# 40-.net
KiCad netlist of a schematic drawn in Altium Designer
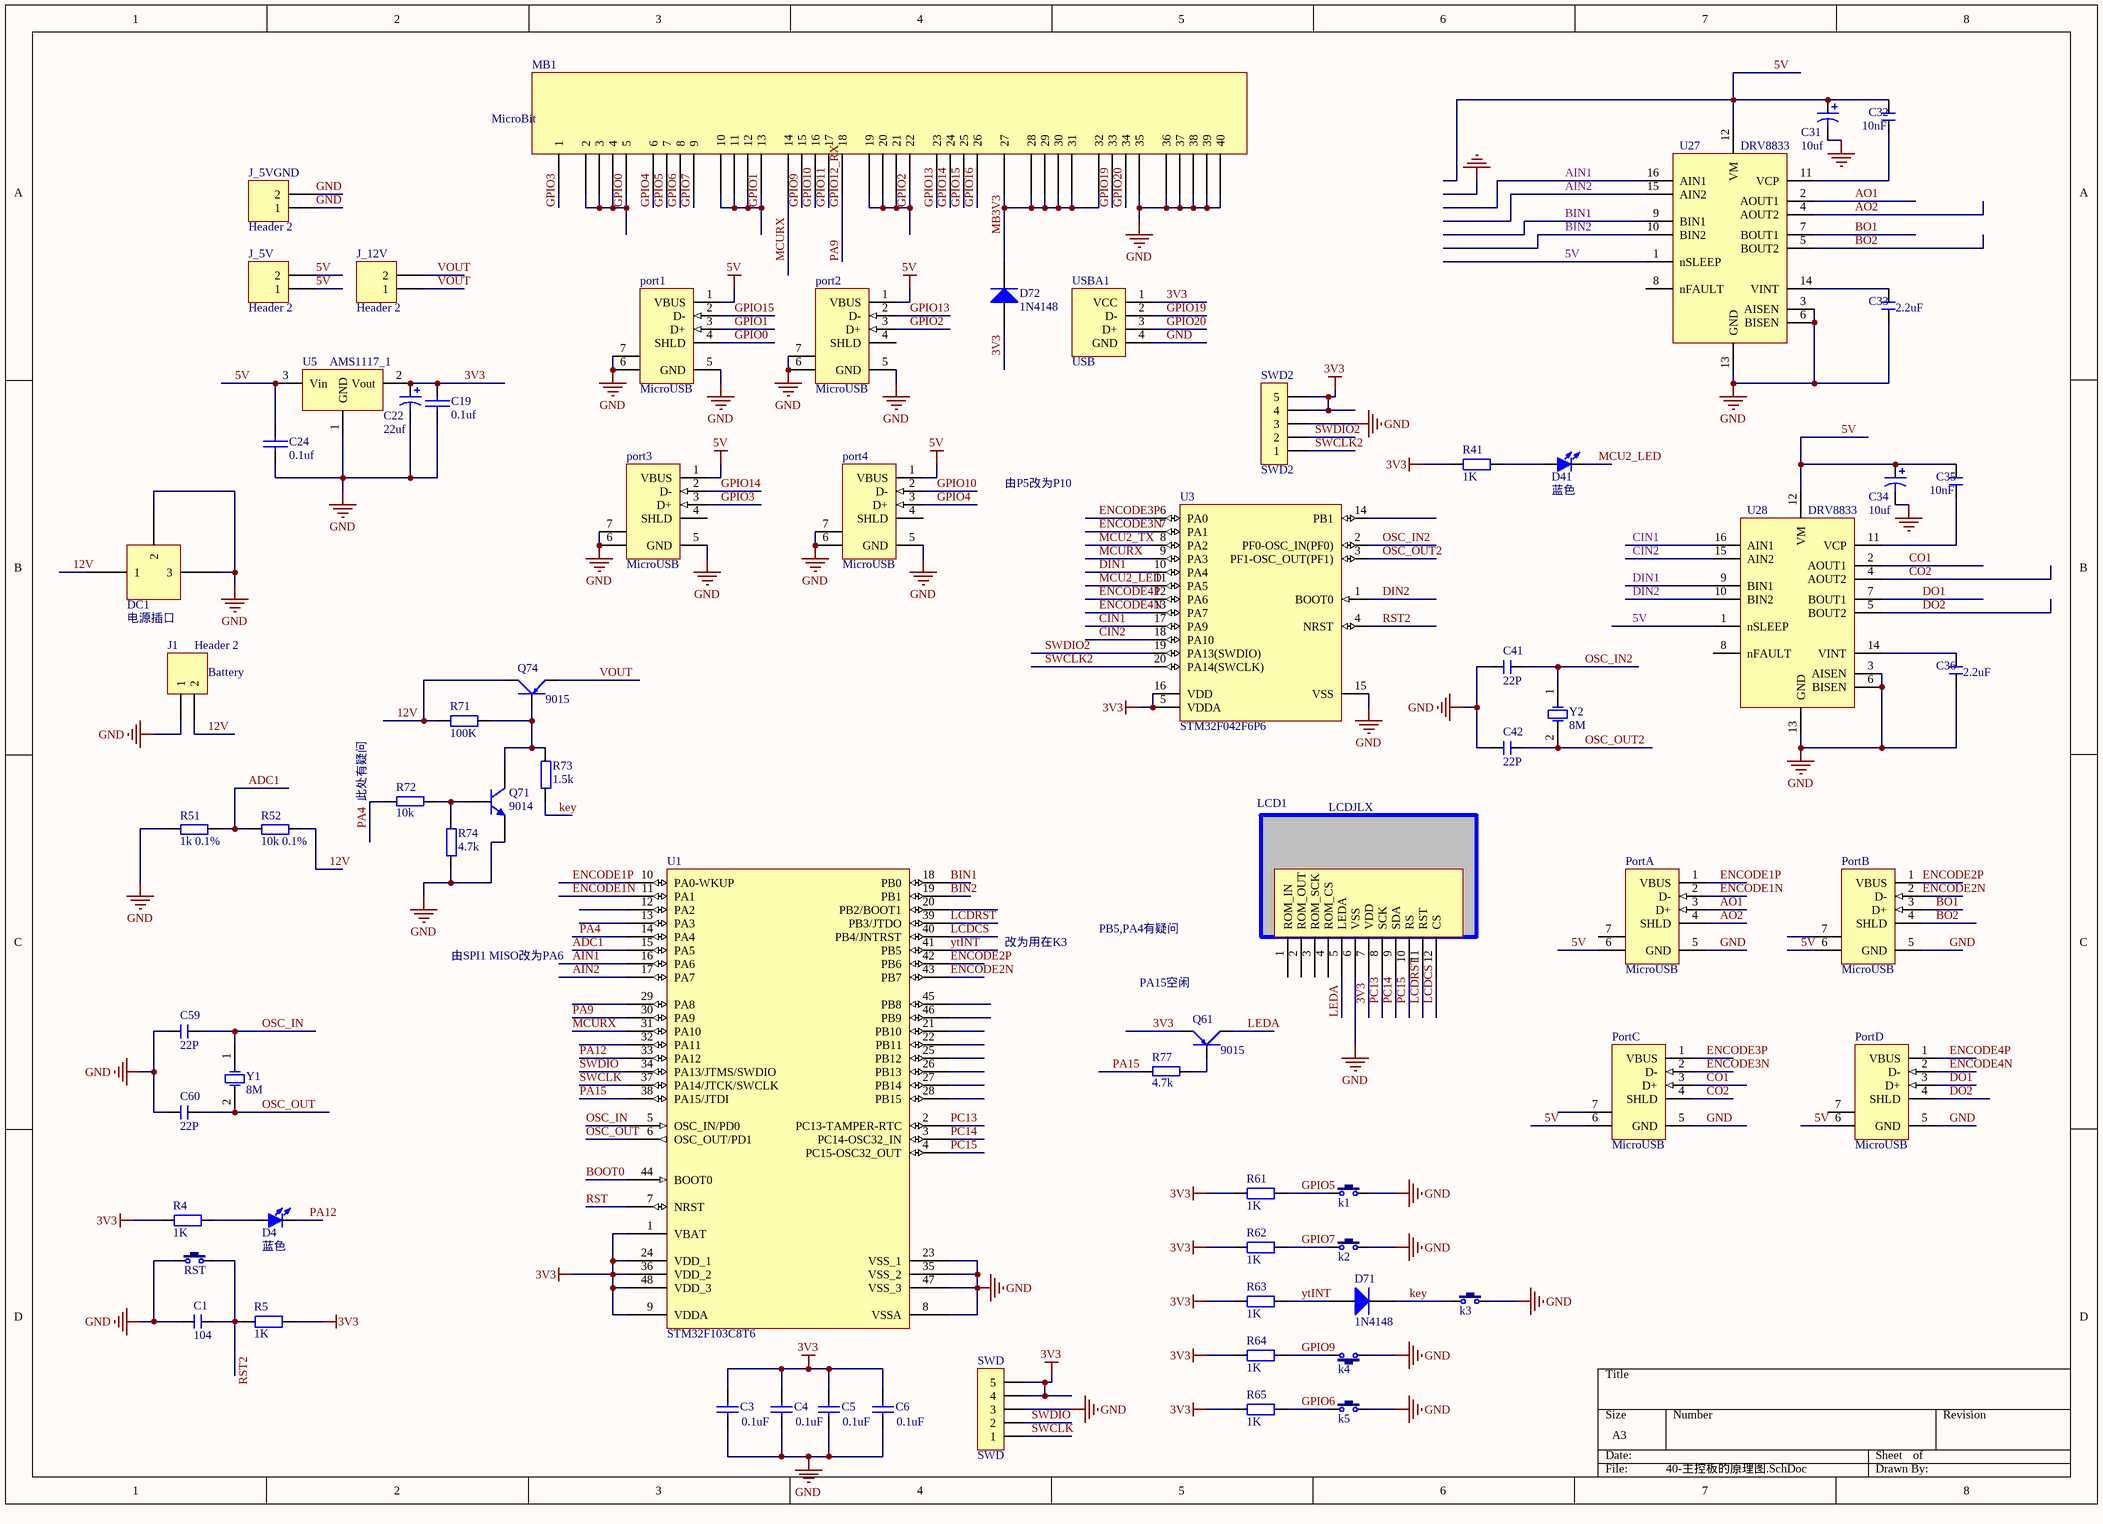
[diagram p0: 40-主控板的原理图.SchDoc]

(export (version "E")
  (design (tool "Eeschema 10.0.6"))
  (components
    (comp (ref "C1")
      (value "104")
      (footprint "C0603")
      (description "无极性贴片电容")
      (libsource (lib "3.1   - 电阻-电容-电感") (part "C"))
    )
    (comp (ref "C3")
      (value "0.1uF")
      (footprint "C0603")
      (description "Capacitor")
      (fields (field (name "Comment") "0.1uf") (field (name "PUBLISHER") "Altium Limited"))
      (libsource (lib "Miscellaneous Devices") (part "Cap"))
    )
    (comp (ref "C4")
      (value "0.1uF")
      (footprint "C0603")
      (description "Capacitor")
      (fields (field (name "Comment") "0.1uf") (field (name "PUBLISHER") "Altium Limited"))
      (libsource (lib "Miscellaneous Devices") (part "Cap"))
    )
    (comp (ref "C5")
      (value "0.1uF")
      (footprint "C0603")
      (description "Capacitor")
      (fields (field (name "Comment") "0.1uf") (field (name "PUBLISHER") "Altium Limited"))
      (libsource (lib "Miscellaneous Devices") (part "Cap"))
    )
    (comp (ref "C6")
      (value "0.1uF")
      (footprint "C0603")
      (description "Capacitor")
      (fields (field (name "Comment") "0.1uf") (field (name "PUBLISHER") "Altium Limited"))
      (libsource (lib "Miscellaneous Devices") (part "Cap"))
    )
    (comp (ref "C19") (value "0.1uf") (footprint "LC-0603_C") (libsource (lib "自创") (part "CAP")))
    (comp (ref "C22")
      (value "22uf")
      (footprint "CD B(3528)")
      (description "Polarized Capacitor (Axial)")
      (fields (field (name "PUBLISHER") "Altium Limited"))
      (libsource (lib "自创") (part "Cap Pol2"))
    )
    (comp (ref "C24") (value "0.1uf") (footprint "LC-0603_C") (libsource (lib "自创") (part "CAP")))
    (comp (ref "C31")
      (value "10uf")
      (footprint "CD B(3528)")
      (description "Polarized Capacitor (Axial)")
      (fields (field (name "PUBLISHER") "Altium Limited"))
      (libsource (lib "自创") (part "Cap Pol2"))
    )
    (comp (ref "C32")
      (value "10nF")
      (footprint "C0603")
      (description "无极性贴片电容")
      (libsource (lib "电阻-电容-电感") (part "C"))
    )
    (comp (ref "C33")
      (value "2.2uF")
      (footprint "C0603")
      (description "无极性贴片电容")
      (libsource (lib "电阻-电容-电感") (part "C"))
    )
    (comp (ref "C34")
      (value "10uf")
      (footprint "CD B(3528)")
      (description "Polarized Capacitor (Axial)")
      (fields (field (name "PUBLISHER") "Altium Limited"))
      (libsource (lib "自创") (part "Cap Pol2"))
    )
    (comp (ref "C35")
      (value "10nF")
      (footprint "C0603")
      (description "无极性贴片电容")
      (libsource (lib "电阻-电容-电感") (part "C"))
    )
    (comp (ref "C36")
      (value "2.2uF")
      (footprint "C0603")
      (description "无极性贴片电容")
      (libsource (lib "电阻-电容-电感") (part "C"))
    )
    (comp (ref "C41")
      (value "22P")
      (footprint "C0603")
      (description "无极性贴片电容")
      (libsource (lib "3.1   - 电阻-电容-电感") (part "C"))
    )
    (comp (ref "C42")
      (value "22P")
      (footprint "C0603")
      (description "无极性贴片电容")
      (libsource (lib "3.1   - 电阻-电容-电感") (part "C"))
    )
    (comp (ref "C59")
      (value "22P")
      (footprint "C0603")
      (description "无极性贴片电容")
      (libsource (lib "3.1   - 电阻-电容-电感") (part "C"))
    )
    (comp (ref "C60")
      (value "22P")
      (footprint "C0603")
      (description "无极性贴片电容")
      (libsource (lib "3.1   - 电阻-电容-电感") (part "C"))
    )
    (comp (ref "D4")
      (value "蓝色")
      (footprint "D0603")
      (description "贴片LED")
      (libsource (lib "9.1   - LED") (part "LED-SMD"))
    )
    (comp (ref "D41")
      (value "蓝色")
      (footprint "D0603")
      (description "贴片LED")
      (libsource (lib "9.1   - LED") (part "LED-SMD"))
    )
    (comp (ref "D71")
      (value "1N4148")
      (footprint "SMD-IN4148")
      (description "High Conductance Fast Diode")
      (fields (field (name "PUBLISHER") "Altium Limited"))
      (libsource (lib "Miscellaneous Devices") (part "Diode 1N4148"))
    )
    (comp (ref "D72")
      (value "1N4148")
      (footprint "SMD-IN4148")
      (description "High Conductance Fast Diode")
      (fields (field (name "PUBLISHER") "Altium Limited"))
      (libsource (lib "Miscellaneous Devices") (part "Diode 1N4148"))
    )
    (comp (ref "DC1") (value "电源插口") (footprint "DC1") (libsource (lib "Schlib1") (part "power_port")))
    (comp (ref "J1")
      (value "Header 2")
      (footprint "HDR1X2")
      (description "Header, 2-Pin")
      (fields (field (name "PUBLISHER") "Altium Limited"))
      (libsource (lib "") (part "Header 2_1"))
    )
    (comp (ref "J_5V")
      (value "Header 2")
      (footprint "HDR1X2")
      (description "Header, 2-Pin")
      (fields (field (name "PUBLISHER") "Altium Limited"))
      (libsource (lib "Miscellaneous Connectors") (part "Header 2"))
    )
    (comp (ref "J_5VGND")
      (value "Header 2")
      (footprint "HDR1X2")
      (description "Header, 2-Pin")
      (fields (field (name "PUBLISHER") "Altium Limited"))
      (libsource (lib "Miscellaneous Connectors") (part "Header 2"))
    )
    (comp (ref "J_12V")
      (value "Header 2")
      (footprint "HDR1X2")
      (description "Header, 2-Pin")
      (fields (field (name "PUBLISHER") "Altium Limited"))
      (libsource (lib "Miscellaneous Connectors") (part "Header 2"))
    )
    (comp (ref "k1")
      (value "3x6x5")
      (footprint "key_4smd")
      (description "3x6轻触开关")
      (libsource (lib "5.1   - 按键-开关") (part "TSW 3x6"))
    )
    (comp (ref "k2")
      (value "3x6x5")
      (footprint "key_4smd")
      (description "3x6轻触开关")
      (libsource (lib "5.1   - 按键-开关") (part "TSW 3x6"))
    )
    (comp (ref "k3")
      (value "3x6x5")
      (footprint "key_4smd")
      (description "3x6轻触开关")
      (libsource (lib "5.1   - 按键-开关") (part "TSW 3x6"))
    )
    (comp (ref "k4")
      (value "3x6x5")
      (footprint "key_4smd")
      (description "3x6轻触开关")
      (libsource (lib "") (part "TSW 3x6_1"))
    )
    (comp (ref "k5")
      (value "3x6x5")
      (footprint "key_4smd")
      (description "3x6轻触开关")
      (libsource (lib "5.1   - 按键-开关") (part "TSW 3x6"))
    )
    (comp (ref "LCD1") (value "LCDJLX") (footprint "LCDLJX-SHU") (libsource (lib "balance") (part "LCDJLX")))
    (comp (ref "MB1") (value "MicroBit") (footprint "IDE1") (libsource (lib "balance") (part "MicroBit")))
    (comp (ref "port1")
      (value "MicroUSB")
      (footprint "USB/SM0.8-6H5")
      (description "USB 2.0, Right Angle, SMT, A Type, Receptacle, 5 Position, Black")
      (fields (field (name "PUBLISHER") "Altium Limited"))
      (libsource (lib "F300") (part "440478-2"))
    )
    (comp (ref "port2")
      (value "MicroUSB")
      (footprint "USB/SM0.8-6H5")
      (description "USB 2.0, Right Angle, SMT, A Type, Receptacle, 5 Position, Black")
      (fields (field (name "PUBLISHER") "Altium Limited"))
      (libsource (lib "F300") (part "440478-2"))
    )
    (comp (ref "port3")
      (value "MicroUSB")
      (footprint "USB/SM0.8-6H5")
      (description "USB 2.0, Right Angle, SMT, A Type, Receptacle, 5 Position, Black")
      (fields (field (name "PUBLISHER") "Altium Limited"))
      (libsource (lib "F300") (part "440478-2"))
    )
    (comp (ref "port4")
      (value "MicroUSB")
      (footprint "USB/SM0.8-6H5")
      (description "USB 2.0, Right Angle, SMT, A Type, Receptacle, 5 Position, Black")
      (fields (field (name "PUBLISHER") "Altium Limited"))
      (libsource (lib "F300") (part "440478-2"))
    )
    (comp (ref "PortA")
      (value "MicroUSB")
      (footprint "USB6P")
      (description "USB 2.0, Right Angle, SMT, A Type, Receptacle, 5 Position, Black")
      (fields (field (name "PUBLISHER") "Altium Limited"))
      (libsource (lib "F300") (part "440478-2"))
    )
    (comp (ref "PortB")
      (value "MicroUSB")
      (footprint "USB6P")
      (description "USB 2.0, Right Angle, SMT, A Type, Receptacle, 5 Position, Black")
      (fields (field (name "PUBLISHER") "Altium Limited"))
      (libsource (lib "F300") (part "440478-2"))
    )
    (comp (ref "PortC")
      (value "MicroUSB")
      (footprint "USB6P")
      (description "USB 2.0, Right Angle, SMT, A Type, Receptacle, 5 Position, Black")
      (fields (field (name "PUBLISHER") "Altium Limited"))
      (libsource (lib "F300") (part "440478-2"))
    )
    (comp (ref "PortD")
      (value "MicroUSB")
      (footprint "USB6P")
      (description "USB 2.0, Right Angle, SMT, A Type, Receptacle, 5 Position, Black")
      (fields (field (name "PUBLISHER") "Altium Limited"))
      (libsource (lib "F300") (part "440478-2"))
    )
    (comp (ref "Q61") (value "9015") (footprint "sot-23r") (libsource (lib "s9015") (part "PNP9015")))
    (comp (ref "Q71")
      (value "9014")
      (footprint "sot-23r")
      (description "NPN Bipolar Transistor")
      (fields (field (name "PUBLISHER") "Altium Limited"))
      (libsource (lib "Miscellaneous Devices") (part "NPN"))
    )
    (comp (ref "Q74") (value "9015") (footprint "sot-23r") (libsource (lib "s9015") (part "PNP9015")))
    (comp (ref "R4")
      (value "1K")
      (footprint "R0603")
      (description "贴片电阻")
      (libsource (lib "3.1   - 电阻-电容-电感") (part "R"))
    )
    (comp (ref "R5")
      (value "1K")
      (footprint "R0603")
      (description "贴片电阻")
      (libsource (lib "3.1   - 电阻-电容-电感") (part "R"))
    )
    (comp (ref "R41")
      (value "1K")
      (footprint "R0603")
      (description "贴片电阻")
      (libsource (lib "3.1   - 电阻-电容-电感") (part "R"))
    )
    (comp (ref "R51") (value "1k 0.1%") (footprint "R0603") (libsource (lib "ATK-RM04") (part "R")))
    (comp (ref "R52") (value "10k 0.1%") (footprint "R0603") (libsource (lib "ATK-RM04") (part "R")))
    (comp (ref "R61")
      (value "1K")
      (footprint "R0603")
      (description "贴片电阻")
      (libsource (lib "3.1   - 电阻-电容-电感") (part "R"))
    )
    (comp (ref "R62")
      (value "1K")
      (footprint "R0603")
      (description "贴片电阻")
      (libsource (lib "3.1   - 电阻-电容-电感") (part "R"))
    )
    (comp (ref "R63")
      (value "1K")
      (footprint "R0603")
      (description "贴片电阻")
      (libsource (lib "3.1   - 电阻-电容-电感") (part "R"))
    )
    (comp (ref "R64")
      (value "1K")
      (footprint "R0603")
      (description "贴片电阻")
      (libsource (lib "3.1   - 电阻-电容-电感") (part "R"))
    )
    (comp (ref "R65")
      (value "1K")
      (footprint "R0603")
      (description "贴片电阻")
      (libsource (lib "3.1   - 电阻-电容-电感") (part "R"))
    )
    (comp (ref "R71")
      (value "100K")
      (footprint "R0603")
      (description "贴片电阻")
      (libsource (lib "3.1   - 电阻-电容-电感") (part "R"))
    )
    (comp (ref "R72") (value "10k") (footprint "R0603") (libsource (lib "ATK-RM04") (part "R")))
    (comp (ref "R73") (value "1.5k") (footprint "R0603") (libsource (lib "ATK-RM04") (part "R")))
    (comp (ref "R74") (value "4.7k") (footprint "R0603") (libsource (lib "ATK-RM04") (part "R")))
    (comp (ref "R77") (value "4.7k") (footprint "R0603") (libsource (lib "ATK-RM04") (part "R")))
    (comp (ref "RST")
      (value "3x6x5")
      (footprint "key_4smd")
      (description "3x6轻触开关")
      (libsource (lib "5.1   - 按键-开关") (part "TSW 3x6"))
    )
    (comp (ref "SWD")
      (value "SWD")
      (footprint "HDR1X5")
      (description "5P接插件")
      (libsource (lib "4.5   - 接插件-脚距2.54") (part "Header 5"))
    )
    (comp (ref "SWD2")
      (value "SWD2")
      (footprint "HDR1X5")
      (description "5P接插件")
      (libsource (lib "4.5   - 接插件-脚距2.54") (part "Header 5"))
    )
    (comp (ref "U1")
      (value "STM32F103C8T6")
      (footprint "LQFP48 7X7_M")
      (description "STM32 ARM-based 32-bit MCU with 64 Kbytes Flash, 48-pin LQFP, Industrial Temperature")
      (fields (field (name "PUBLISHER") "Altium Limited"))
      (libsource (lib "ST Microcontroller 32-Bit STM32") (part "STM32F103C8T6"))
    )
    (comp (ref "U3")
      (value "STM32F042F6P6")
      (footprint "STM-TSSOP20_N")
      (fields (field (name "PARTNUMBER") "STM32F030F4P6"))
      (libsource (lib "STMicroelectronics STM32 F0") (part "STM32F030F4P6"))
    )
    (comp (ref "U5")
      (value "AMS1117_1")
      (footprint "LC-SOT-223")
      (description "3.3V电压转换器AMS1117")
      (libsource (lib "自创") (part "AMS1117_1"))
    )
    (comp (ref "U27")
      (value "DRV8833")
      (footprint "TSSOP16_M")
      (description "双H-桥电机驱动")
      (libsource (lib "IC芯片") (part "DRV8833_NEW"))
    )
    (comp (ref "U28")
      (value "DRV8833")
      (footprint "TSSOP16_M")
      (description "双H-桥电机驱动")
      (libsource (lib "IC芯片") (part "DRV8833_NEW"))
    )
    (comp (ref "USBA1") (value "USB") (footprint "USB-A") (libsource (lib "PP_SCHlib_Altium") (part "USB")))
    (comp (ref "Y1")
      (value "8M")
      (footprint "XTAL_US")
      (description "Crystal Oscillator")
      (fields (field (name "PUBLISHER") "Altium Limited"))
      (libsource (lib "Miscellaneous Devices") (part "XTAL"))
    )
    (comp (ref "Y2")
      (value "8M")
      (footprint "XTAL_US")
      (description "Crystal Oscillator")
      (fields (field (name "PUBLISHER") "Altium Limited"))
      (libsource (lib "Miscellaneous Devices") (part "XTAL"))
    )
  )
  (nets
    (net (code "1") (name "/12V") (class "Default")
      (node (ref "DC1") (pin "1") (pinfunction "1_1") (pintype "passive"))
      (node (ref "J1") (pin "2") (pinfunction "2_2") (pintype "passive"))
      (node (ref "Q74") (pin "3") (pinfunction "C_3") (pintype "passive"))
      (node (ref "R52") (pin "2") (pintype "passive"))
      (node (ref "R71") (pin "1") (pinfunction "1_1") (pintype "passive"))
    )
    (net (code "2") (name "/ADC1") (class "Default")
      (node (ref "R51") (pin "2") (pintype "passive"))
      (node (ref "R52") (pin "1") (pintype "passive"))
      (node (ref "U1") (pin "15") (pinfunction "PA5_15") (pintype "bidirectional"))
    )
    (net (code "3") (name "/AIN1") (class "Default")
      (node (ref "U1") (pin "16") (pinfunction "PA6_16") (pintype "bidirectional"))
      (node (ref "U27") (pin "16") (pinfunction "AIN1_16") (pintype "passive"))
    )
    (net (code "4") (name "/AIN2") (class "Default")
      (node (ref "U1") (pin "17") (pinfunction "PA7_17") (pintype "bidirectional"))
      (node (ref "U27") (pin "15") (pinfunction "AIN2_15") (pintype "passive"))
    )
    (net (code "5") (name "/AO1") (class "Default")
      (node (ref "PortA") (pin "3") (pinfunction "D+_3") (pintype "input"))
      (node (ref "U27") (pin "2") (pinfunction "AOUT1_2") (pintype "passive"))
    )
    (net (code "6") (name "/AO2") (class "Default")
      (node (ref "PortA") (pin "4") (pinfunction "SHLD_4") (pintype "passive"))
      (node (ref "U27") (pin "4") (pinfunction "AOUT2_4") (pintype "passive"))
    )
    (net (code "7") (name "/BIN1") (class "Default")
      (node (ref "U1") (pin "18") (pinfunction "PB0_18") (pintype "bidirectional"))
      (node (ref "U27") (pin "9") (pinfunction "BIN1_9") (pintype "passive"))
    )
    (net (code "8") (name "/BIN2") (class "Default")
      (node (ref "U1") (pin "19") (pinfunction "PB1_19") (pintype "bidirectional"))
      (node (ref "U27") (pin "10") (pinfunction "BIN2_10") (pintype "passive"))
    )
    (net (code "9") (name "/BO1") (class "Default")
      (node (ref "PortB") (pin "3") (pinfunction "D+_3") (pintype "input"))
      (node (ref "U27") (pin "7") (pinfunction "BOUT1_7") (pintype "passive"))
    )
    (net (code "10") (name "/BO2") (class "Default")
      (node (ref "PortB") (pin "4") (pinfunction "SHLD_4") (pintype "passive"))
      (node (ref "U27") (pin "5") (pinfunction "BOUT2_5") (pintype "passive"))
    )
    (net (code "11") (name "/BOOT0") (class "Default")
      (node (ref "U1") (pin "44") (pinfunction "BOOT0_44") (pintype "input"))
    )
    (net (code "12") (name "/CIN1") (class "Default")
      (node (ref "U28") (pin "16") (pinfunction "AIN1_16") (pintype "passive"))
      (node (ref "U3") (pin "17") (pinfunction "PA9_17") (pintype "bidirectional"))
    )
    (net (code "13") (name "/CIN2") (class "Default")
      (node (ref "U28") (pin "15") (pinfunction "AIN2_15") (pintype "passive"))
      (node (ref "U3") (pin "18") (pinfunction "PA10_18") (pintype "bidirectional"))
    )
    (net (code "14") (name "/CO1") (class "Default")
      (node (ref "PortC") (pin "3") (pinfunction "D+_3") (pintype "input"))
      (node (ref "U28") (pin "2") (pinfunction "AOUT1_2") (pintype "passive"))
    )
    (net (code "15") (name "/CO2") (class "Default")
      (node (ref "PortC") (pin "4") (pinfunction "SHLD_4") (pintype "passive"))
      (node (ref "U28") (pin "4") (pinfunction "AOUT2_4") (pintype "passive"))
    )
    (net (code "16") (name "/DIN1") (class "Default")
      (node (ref "U28") (pin "9") (pinfunction "BIN1_9") (pintype "passive"))
      (node (ref "U3") (pin "10") (pinfunction "PA4_10") (pintype "bidirectional"))
    )
    (net (code "17") (name "/DIN2") (class "Default")
      (node (ref "U28") (pin "10") (pinfunction "BIN2_10") (pintype "passive"))
      (node (ref "U3") (pin "1") (pinfunction "BOOT0_1") (pintype "input"))
    )
    (net (code "18") (name "/DO1") (class "Default")
      (node (ref "PortD") (pin "3") (pinfunction "D+_3") (pintype "input"))
      (node (ref "U28") (pin "7") (pinfunction "BOUT1_7") (pintype "passive"))
    )
    (net (code "19") (name "/DO2") (class "Default")
      (node (ref "PortD") (pin "4") (pinfunction "SHLD_4") (pintype "passive"))
      (node (ref "U28") (pin "5") (pinfunction "BOUT2_5") (pintype "passive"))
    )
    (net (code "20") (name "/ENCODE1N") (class "Default")
      (node (ref "PortA") (pin "2") (pinfunction "D-_2") (pintype "input"))
      (node (ref "U1") (pin "11") (pinfunction "PA1_11") (pintype "bidirectional"))
    )
    (net (code "21") (name "/ENCODE1P") (class "Default")
      (node (ref "PortA") (pin "1") (pinfunction "VBUS_1") (pintype "power_in"))
      (node (ref "U1") (pin "10") (pinfunction "PA0-WKUP_10") (pintype "bidirectional"))
    )
    (net (code "22") (name "/ENCODE2N") (class "Default")
      (node (ref "PortB") (pin "2") (pinfunction "D-_2") (pintype "input"))
      (node (ref "U1") (pin "43") (pinfunction "PB7_43") (pintype "bidirectional"))
    )
    (net (code "23") (name "/ENCODE2P") (class "Default")
      (node (ref "PortB") (pin "1") (pinfunction "VBUS_1") (pintype "power_in"))
      (node (ref "U1") (pin "42") (pinfunction "PB6_42") (pintype "bidirectional"))
    )
    (net (code "24") (name "/ENCODE3N") (class "Default")
      (node (ref "PortC") (pin "2") (pinfunction "D-_2") (pintype "input"))
      (node (ref "U3") (pin "7") (pinfunction "PA1_7") (pintype "bidirectional"))
    )
    (net (code "25") (name "/ENCODE3P") (class "Default")
      (node (ref "PortC") (pin "1") (pinfunction "VBUS_1") (pintype "power_in"))
      (node (ref "U3") (pin "6") (pinfunction "PA0_6") (pintype "bidirectional"))
    )
    (net (code "26") (name "/ENCODE4N") (class "Default")
      (node (ref "PortD") (pin "2") (pinfunction "D-_2") (pintype "input"))
      (node (ref "U3") (pin "13") (pinfunction "PA7_13") (pintype "bidirectional"))
    )
    (net (code "27") (name "/ENCODE4P") (class "Default")
      (node (ref "PortD") (pin "1") (pinfunction "VBUS_1") (pintype "power_in"))
      (node (ref "U3") (pin "12") (pinfunction "PA6_12") (pintype "bidirectional"))
    )
    (net (code "28") (name "/GPIO0") (class "Default")
      (node (ref "MB1") (pin "2") (pinfunction "2_2") (pintype "passive"))
      (node (ref "MB1") (pin "3") (pinfunction "3_3") (pintype "passive"))
      (node (ref "MB1") (pin "4") (pinfunction "4_4") (pintype "passive"))
      (node (ref "MB1") (pin "5") (pinfunction "5_5") (pintype "passive"))
      (node (ref "port1") (pin "4") (pinfunction "SHLD_4") (pintype "passive"))
    )
    (net (code "29") (name "/GPIO1") (class "Default")
      (node (ref "MB1") (pin "10") (pinfunction "10_10") (pintype "passive"))
      (node (ref "MB1") (pin "11") (pinfunction "11_11") (pintype "passive"))
      (node (ref "MB1") (pin "12") (pinfunction "12_12") (pintype "passive"))
      (node (ref "MB1") (pin "13") (pinfunction "13_13") (pintype "passive"))
      (node (ref "port1") (pin "3") (pinfunction "D+_3") (pintype "input"))
    )
    (net (code "30") (name "/GPIO2") (class "Default")
      (node (ref "MB1") (pin "19") (pinfunction "19_19") (pintype "passive"))
      (node (ref "MB1") (pin "20") (pinfunction "20_20") (pintype "passive"))
      (node (ref "MB1") (pin "21") (pinfunction "21_21") (pintype "passive"))
      (node (ref "MB1") (pin "22") (pinfunction "22_22") (pintype "passive"))
      (node (ref "port2") (pin "3") (pinfunction "D+_3") (pintype "input"))
    )
    (net (code "31") (name "/GPIO3") (class "Default")
      (node (ref "MB1") (pin "1") (pinfunction "1_1") (pintype "passive"))
      (node (ref "port3") (pin "3") (pinfunction "D+_3") (pintype "input"))
    )
    (net (code "32") (name "/GPIO4") (class "Default")
      (node (ref "MB1") (pin "6") (pinfunction "6_6") (pintype "passive"))
      (node (ref "port4") (pin "3") (pinfunction "D+_3") (pintype "input"))
    )
    (net (code "33") (name "/GPIO5") (class "Default")
      (node (ref "MB1") (pin "7") (pinfunction "7_7") (pintype "passive"))
      (node (ref "R61") (pin "2") (pinfunction "2_2") (pintype "passive"))
      (node (ref "k1") (pin "1") (pinfunction "1_1") (pintype "passive"))
    )
    (net (code "34") (name "/GPIO6") (class "Default")
      (node (ref "MB1") (pin "8") (pinfunction "8_8") (pintype "passive"))
      (node (ref "R65") (pin "2") (pinfunction "2_2") (pintype "passive"))
      (node (ref "k5") (pin "1") (pinfunction "1_1") (pintype "passive"))
    )
    (net (code "35") (name "/GPIO7") (class "Default")
      (node (ref "MB1") (pin "9") (pinfunction "9_9") (pintype "passive"))
      (node (ref "R62") (pin "2") (pinfunction "2_2") (pintype "passive"))
      (node (ref "k2") (pin "1") (pinfunction "1_1") (pintype "passive"))
    )
    (net (code "36") (name "/GPIO9") (class "Default")
      (node (ref "MB1") (pin "15") (pinfunction "15_15") (pintype "passive"))
      (node (ref "R64") (pin "2") (pinfunction "2_2") (pintype "passive"))
      (node (ref "k4") (pin "2") (pinfunction "2_2") (pintype "passive"))
    )
    (net (code "37") (name "/GPIO10") (class "Default")
      (node (ref "MB1") (pin "16") (pinfunction "16_16") (pintype "passive"))
      (node (ref "port4") (pin "2") (pinfunction "D-_2") (pintype "input"))
    )
    (net (code "38") (name "/GPIO11") (class "Default")
      (node (ref "MB1") (pin "17") (pinfunction "17_17") (pintype "passive"))
    )
    (net (code "39") (name "/GPIO12_RX") (class "Default")
      (node (ref "MB1") (pin "18") (pinfunction "18_18") (pintype "passive"))
      (node (ref "U1") (pin "30") (pinfunction "PA9_30") (pintype "bidirectional"))
    )
    (net (code "40") (name "/GPIO13") (class "Default")
      (node (ref "MB1") (pin "23") (pinfunction "23_23") (pintype "passive"))
      (node (ref "port2") (pin "2") (pinfunction "D-_2") (pintype "input"))
    )
    (net (code "41") (name "/GPIO14") (class "Default")
      (node (ref "MB1") (pin "24") (pinfunction "24_24") (pintype "passive"))
      (node (ref "port3") (pin "2") (pinfunction "D-_2") (pintype "input"))
    )
    (net (code "42") (name "/GPIO15") (class "Default")
      (node (ref "MB1") (pin "25") (pinfunction "25_25") (pintype "passive"))
      (node (ref "port1") (pin "2") (pinfunction "D-_2") (pintype "input"))
    )
    (net (code "43") (name "/GPIO16") (class "Default")
      (node (ref "MB1") (pin "26") (pinfunction "26_26") (pintype "passive"))
    )
    (net (code "44") (name "/GPIO19") (class "Default")
      (node (ref "MB1") (pin "33") (pinfunction "33_33") (pintype "passive"))
      (node (ref "USBA1") (pin "2") (pinfunction "D-_2") (pintype "passive"))
    )
    (net (code "45") (name "/GPIO20") (class "Default")
      (node (ref "MB1") (pin "34") (pinfunction "34_34") (pintype "passive"))
      (node (ref "USBA1") (pin "3") (pinfunction "D+_3") (pintype "passive"))
    )
    (net (code "46") (name "/LCDCS") (class "Default")
      (node (ref "LCD1") (pin "12") (pinfunction "CS_12") (pintype "passive"))
      (node (ref "U1") (pin "40") (pinfunction "PB4/JNTRST_40") (pintype "bidirectional"))
    )
    (net (code "47") (name "/LCDRST") (class "Default")
      (node (ref "LCD1") (pin "11") (pinfunction "RST_11") (pintype "passive"))
      (node (ref "U1") (pin "39") (pinfunction "PB3/JTDO_39") (pintype "bidirectional"))
    )
    (net (code "48") (name "/LEDA") (class "Default")
      (node (ref "LCD1") (pin "5") (pinfunction "LEDA_5") (pintype "passive"))
      (node (ref "Q61") (pin "3") (pinfunction "C_3") (pintype "passive"))
    )
    (net (code "49") (name "/MB3V3") (class "Default")
      (node (ref "D72") (pin "2") (pinfunction "K_2") (pintype "passive"))
      (node (ref "MB1") (pin "27") (pinfunction "27_27") (pintype "passive"))
      (node (ref "MB1") (pin "28") (pinfunction "28_28") (pintype "passive"))
      (node (ref "MB1") (pin "29") (pinfunction "29_29") (pintype "passive"))
      (node (ref "MB1") (pin "30") (pinfunction "30_30") (pintype "passive"))
      (node (ref "MB1") (pin "31") (pinfunction "31_31") (pintype "passive"))
      (node (ref "MB1") (pin "32") (pinfunction "32_32") (pintype "passive"))
    )
    (net (code "50") (name "/MCU2_LED") (class "Default")
      (node (ref "D41") (pin "2") (pinfunction "K_2") (pintype "passive"))
      (node (ref "U3") (pin "11") (pinfunction "PA5_11") (pintype "bidirectional"))
    )
    (net (code "51") (name "/MCU2_TX") (class "Default")
      (node (ref "U3") (pin "8") (pinfunction "PA2_8") (pintype "bidirectional"))
    )
    (net (code "52") (name "/MCURX") (class "Default")
      (node (ref "MB1") (pin "14") (pinfunction "14_14") (pintype "passive"))
      (node (ref "U1") (pin "31") (pinfunction "PA10_31") (pintype "bidirectional"))
      (node (ref "U3") (pin "9") (pinfunction "PA3_9") (pintype "bidirectional"))
    )
    (net (code "53") (name "/OSC_IN") (class "Default")
      (node (ref "C59") (pin "2") (pinfunction "2_2") (pintype "passive"))
      (node (ref "U1") (pin "5") (pinfunction "OSC_IN/PD0_5") (pintype "input"))
      (node (ref "Y1") (pin "1") (pinfunction "OSC1_1") (pintype "passive"))
    )
    (net (code "54") (name "/OSC_IN2") (class "Default")
      (node (ref "C41") (pin "2") (pinfunction "2_2") (pintype "passive"))
      (node (ref "U3") (pin "2") (pinfunction "PF0-OSC_IN(PF0)_2") (pintype "bidirectional"))
      (node (ref "Y2") (pin "1") (pinfunction "OSC1_1") (pintype "passive"))
    )
    (net (code "55") (name "/OSC_OUT") (class "Default")
      (node (ref "C60") (pin "2") (pinfunction "2_2") (pintype "passive"))
      (node (ref "U1") (pin "6") (pinfunction "OSC_OUT/PD1_6") (pintype "output"))
      (node (ref "Y1") (pin "2") (pinfunction "OSC2_2") (pintype "passive"))
    )
    (net (code "56") (name "/OSC_OUT2") (class "Default")
      (node (ref "C42") (pin "2") (pinfunction "2_2") (pintype "passive"))
      (node (ref "U3") (pin "3") (pinfunction "PF1-OSC_OUT(PF1)_3") (pintype "bidirectional"))
      (node (ref "Y2") (pin "2") (pinfunction "OSC2_2") (pintype "passive"))
    )
    (net (code "57") (name "/PA4") (class "Default")
      (node (ref "R72") (pin "2") (pintype "passive"))
      (node (ref "U1") (pin "14") (pinfunction "PA4_14") (pintype "bidirectional"))
    )
    (net (code "58") (name "/PA12") (class "Default")
      (node (ref "D4") (pin "2") (pinfunction "K_2") (pintype "passive"))
      (node (ref "U1") (pin "33") (pinfunction "PA12_33") (pintype "bidirectional"))
    )
    (net (code "59") (name "/PA15") (class "Default")
      (node (ref "R77") (pin "2") (pintype "passive"))
      (node (ref "U1") (pin "38") (pinfunction "PA15/JTDI_38") (pintype "bidirectional"))
    )
    (net (code "60") (name "/PC13") (class "Default")
      (node (ref "LCD1") (pin "8") (pinfunction "SCK_8") (pintype "passive"))
      (node (ref "U1") (pin "2") (pinfunction "PC13-TAMPER-RTC_2") (pintype "bidirectional"))
    )
    (net (code "61") (name "/PC14") (class "Default")
      (node (ref "LCD1") (pin "9") (pinfunction "SDA_9") (pintype "passive"))
      (node (ref "U1") (pin "3") (pinfunction "PC14-OSC32_IN_3") (pintype "bidirectional"))
    )
    (net (code "62") (name "/PC15") (class "Default")
      (node (ref "LCD1") (pin "10") (pinfunction "RS_10") (pintype "passive"))
      (node (ref "U1") (pin "4") (pinfunction "PC15-OSC32_OUT_4") (pintype "bidirectional"))
    )
    (net (code "63") (name "/RST") (class "Default")
      (node (ref "U1") (pin "7") (pinfunction "NRST_7") (pintype "bidirectional"))
    )
    (net (code "64") (name "/RST2") (class "Default")
      (node (ref "C1") (pin "2") (pinfunction "2_2") (pintype "passive"))
      (node (ref "R5") (pin "1") (pinfunction "1_1") (pintype "passive"))
      (node (ref "RST") (pin "2") (pinfunction "2_2") (pintype "passive"))
      (node (ref "U3") (pin "4") (pinfunction "NRST_4") (pintype "bidirectional"))
    )
    (net (code "65") (name "/SWCLK") (class "Default")
      (node (ref "SWD") (pin "1") (pinfunction "1_1") (pintype "passive"))
      (node (ref "U1") (pin "37") (pinfunction "PA14/JTCK/SWCLK_37") (pintype "bidirectional"))
    )
    (net (code "66") (name "/SWCLK2") (class "Default")
      (node (ref "SWD2") (pin "1") (pinfunction "1_1") (pintype "passive"))
      (node (ref "U3") (pin "20") (pinfunction "PA14(SWCLK)_20") (pintype "bidirectional"))
    )
    (net (code "67") (name "/SWDIO") (class "Default")
      (node (ref "SWD") (pin "2") (pinfunction "2_2") (pintype "passive"))
      (node (ref "U1") (pin "34") (pinfunction "PA13/JTMS/SWDIO_34") (pintype "bidirectional"))
    )
    (net (code "68") (name "/SWDIO2") (class "Default")
      (node (ref "SWD2") (pin "2") (pinfunction "2_2") (pintype "passive"))
      (node (ref "U3") (pin "19") (pinfunction "PA13(SWDIO)_19") (pintype "bidirectional"))
    )
    (net (code "69") (name "/VOUT") (class "Default")
      (node (ref "J_12V") (pin "1") (pinfunction "1_1") (pintype "passive"))
      (node (ref "J_12V") (pin "2") (pinfunction "2_2") (pintype "passive"))
      (node (ref "Q74") (pin "2") (pinfunction "E_2") (pintype "passive"))
    )
    (net (code "70") (name "/key") (class "Default")
      (node (ref "D71") (pin "2") (pinfunction "K_2") (pintype "passive"))
      (node (ref "R73") (pin "1") (pintype "passive"))
      (node (ref "k3") (pin "1") (pinfunction "1_1") (pintype "passive"))
    )
    (net (code "71") (name "/ytINT") (class "Default")
      (node (ref "D71") (pin "1") (pinfunction "A_1") (pintype "passive"))
      (node (ref "R63") (pin "2") (pinfunction "2_2") (pintype "passive"))
      (node (ref "U1") (pin "41") (pinfunction "PB5_41") (pintype "bidirectional"))
    )
    (net (code "72") (name "3V3") (class "Default")
      (node (ref "C19") (pin "2") (pinfunction "2_2") (pintype "passive"))
      (node (ref "C22") (pin "1") (pinfunction "1_1") (pintype "passive"))
      (node (ref "C3") (pin "2") (pinfunction "2_2") (pintype "passive"))
      (node (ref "C4") (pin "2") (pinfunction "2_2") (pintype "passive"))
      (node (ref "C5") (pin "2") (pinfunction "2_2") (pintype "passive"))
      (node (ref "C6") (pin "2") (pinfunction "2_2") (pintype "passive"))
      (node (ref "D72") (pin "1") (pinfunction "A_1") (pintype "passive"))
      (node (ref "LCD1") (pin "7") (pinfunction "VDD_7") (pintype "passive"))
      (node (ref "Q61") (pin "2") (pinfunction "E_2") (pintype "passive"))
      (node (ref "R4") (pin "1") (pinfunction "1_1") (pintype "passive"))
      (node (ref "R41") (pin "1") (pinfunction "1_1") (pintype "passive"))
      (node (ref "R5") (pin "2") (pinfunction "2_2") (pintype "passive"))
      (node (ref "R61") (pin "1") (pinfunction "1_1") (pintype "passive"))
      (node (ref "R62") (pin "1") (pinfunction "1_1") (pintype "passive"))
      (node (ref "R63") (pin "1") (pinfunction "1_1") (pintype "passive"))
      (node (ref "R64") (pin "1") (pinfunction "1_1") (pintype "passive"))
      (node (ref "R65") (pin "1") (pinfunction "1_1") (pintype "passive"))
      (node (ref "SWD") (pin "4") (pinfunction "4_4") (pintype "passive"))
      (node (ref "SWD") (pin "5") (pinfunction "5_5") (pintype "passive"))
      (node (ref "SWD2") (pin "4") (pinfunction "4_4") (pintype "passive"))
      (node (ref "SWD2") (pin "5") (pinfunction "5_5") (pintype "passive"))
      (node (ref "U1") (pin "1") (pinfunction "VBAT_1") (pintype "power_in"))
      (node (ref "U1") (pin "24") (pinfunction "VDD_1_24") (pintype "power_in"))
      (node (ref "U1") (pin "36") (pinfunction "VDD_2_36") (pintype "power_in"))
      (node (ref "U1") (pin "48") (pinfunction "VDD_3_48") (pintype "power_in"))
      (node (ref "U1") (pin "9") (pinfunction "VDDA_9") (pintype "power_in"))
      (node (ref "U3") (pin "16") (pinfunction "VDD_16") (pintype "power_in"))
      (node (ref "U3") (pin "5") (pinfunction "VDDA_5") (pintype "power_in"))
      (node (ref "U5") (pin "2") (pinfunction "Vout_2") (pintype "passive"))
      (node (ref "USBA1") (pin "1") (pinfunction "VCC_1") (pintype "passive"))
    )
    (net (code "73") (name "5V") (class "Default")
      (node (ref "C24") (pin "2") (pinfunction "2_2") (pintype "passive"))
      (node (ref "C31") (pin "1") (pinfunction "1_1") (pintype "passive"))
      (node (ref "C32") (pin "2") (pinfunction "2_2") (pintype "passive"))
      (node (ref "C34") (pin "1") (pinfunction "1_1") (pintype "passive"))
      (node (ref "C35") (pin "2") (pinfunction "2_2") (pintype "passive"))
      (node (ref "J_5V") (pin "1") (pinfunction "1_1") (pintype "passive"))
      (node (ref "J_5V") (pin "2") (pinfunction "2_2") (pintype "passive"))
      (node (ref "PortA") (pin "6") (pinfunction "SHLD_6") (pintype "passive"))
      (node (ref "PortB") (pin "6") (pinfunction "SHLD_6") (pintype "passive"))
      (node (ref "PortC") (pin "6") (pinfunction "SHLD_6") (pintype "passive"))
      (node (ref "PortD") (pin "6") (pinfunction "SHLD_6") (pintype "passive"))
      (node (ref "U27") (pin "1") (pinfunction "nSLEEP_1") (pintype "passive"))
      (node (ref "U27") (pin "12") (pinfunction "VM_12") (pintype "passive"))
      (node (ref "U28") (pin "1") (pinfunction "nSLEEP_1") (pintype "passive"))
      (node (ref "U28") (pin "12") (pinfunction "VM_12") (pintype "passive"))
      (node (ref "U5") (pin "3") (pinfunction "Vin_3") (pintype "passive"))
      (node (ref "port1") (pin "1") (pinfunction "VBUS_1") (pintype "power_in"))
      (node (ref "port2") (pin "1") (pinfunction "VBUS_1") (pintype "power_in"))
      (node (ref "port3") (pin "1") (pinfunction "VBUS_1") (pintype "power_in"))
      (node (ref "port4") (pin "1") (pinfunction "VBUS_1") (pintype "power_in"))
    )
    (net (code "74") (name "GND") (class "Default")
      (node (ref "C1") (pin "1") (pinfunction "1_1") (pintype "passive"))
      (node (ref "C19") (pin "1") (pinfunction "1_1") (pintype "passive"))
      (node (ref "C22") (pin "2") (pinfunction "2_2") (pintype "passive"))
      (node (ref "C24") (pin "1") (pinfunction "1_1") (pintype "passive"))
      (node (ref "C3") (pin "1") (pinfunction "1_1") (pintype "passive"))
      (node (ref "C31") (pin "2") (pinfunction "2_2") (pintype "passive"))
      (node (ref "C33") (pin "1") (pinfunction "1_1") (pintype "passive"))
      (node (ref "C34") (pin "2") (pinfunction "2_2") (pintype "passive"))
      (node (ref "C36") (pin "1") (pinfunction "1_1") (pintype "passive"))
      (node (ref "C4") (pin "1") (pinfunction "1_1") (pintype "passive"))
      (node (ref "C41") (pin "1") (pinfunction "1_1") (pintype "passive"))
      (node (ref "C42") (pin "1") (pinfunction "1_1") (pintype "passive"))
      (node (ref "C5") (pin "1") (pinfunction "1_1") (pintype "passive"))
      (node (ref "C59") (pin "1") (pinfunction "1_1") (pintype "passive"))
      (node (ref "C6") (pin "1") (pinfunction "1_1") (pintype "passive"))
      (node (ref "C60") (pin "1") (pinfunction "1_1") (pintype "passive"))
      (node (ref "DC1") (pin "2") (pinfunction "2_2") (pintype "passive"))
      (node (ref "DC1") (pin "3") (pinfunction "3_3") (pintype "passive"))
      (node (ref "J1") (pin "1") (pinfunction "1_1") (pintype "passive"))
      (node (ref "J_5VGND") (pin "1") (pinfunction "1_1") (pintype "passive"))
      (node (ref "J_5VGND") (pin "2") (pinfunction "2_2") (pintype "passive"))
      (node (ref "LCD1") (pin "6") (pinfunction "VSS_6") (pintype "passive"))
      (node (ref "MB1") (pin "35") (pinfunction "35_35") (pintype "passive"))
      (node (ref "MB1") (pin "36") (pinfunction "36_36") (pintype "passive"))
      (node (ref "MB1") (pin "37") (pinfunction "37_37") (pintype "passive"))
      (node (ref "MB1") (pin "38") (pinfunction "38_38") (pintype "passive"))
      (node (ref "MB1") (pin "39") (pinfunction "39_39") (pintype "passive"))
      (node (ref "MB1") (pin "40") (pinfunction "40_40") (pintype "passive"))
      (node (ref "PortA") (pin "5") (pinfunction "GND_5") (pintype "power_in"))
      (node (ref "PortB") (pin "5") (pinfunction "GND_5") (pintype "power_in"))
      (node (ref "PortC") (pin "5") (pinfunction "GND_5") (pintype "power_in"))
      (node (ref "PortD") (pin "5") (pinfunction "GND_5") (pintype "power_in"))
      (node (ref "Q71") (pin "2") (pinfunction "E_2") (pintype "passive"))
      (node (ref "R51") (pin "1") (pintype "passive"))
      (node (ref "R74") (pin "1") (pintype "passive"))
      (node (ref "RST") (pin "1") (pinfunction "1_1") (pintype "passive"))
      (node (ref "SWD") (pin "3") (pinfunction "3_3") (pintype "passive"))
      (node (ref "SWD2") (pin "3") (pinfunction "3_3") (pintype "passive"))
      (node (ref "U1") (pin "23") (pinfunction "VSS_1_23") (pintype "power_in"))
      (node (ref "U1") (pin "35") (pinfunction "VSS_2_35") (pintype "power_in"))
      (node (ref "U1") (pin "47") (pinfunction "VSS_3_47") (pintype "power_in"))
      (node (ref "U1") (pin "8") (pinfunction "VSSA_8") (pintype "power_in"))
      (node (ref "U27") (pin "13") (pinfunction "GND_13") (pintype "passive"))
      (node (ref "U27") (pin "3") (pinfunction "AISEN_3") (pintype "passive"))
      (node (ref "U27") (pin "6") (pinfunction "BISEN_6") (pintype "passive"))
      (node (ref "U28") (pin "13") (pinfunction "GND_13") (pintype "passive"))
      (node (ref "U28") (pin "3") (pinfunction "AISEN_3") (pintype "passive"))
      (node (ref "U28") (pin "6") (pinfunction "BISEN_6") (pintype "passive"))
      (node (ref "U3") (pin "15") (pinfunction "VSS_15") (pintype "power_in"))
      (node (ref "U5") (pin "1") (pinfunction "GND_1") (pintype "passive"))
      (node (ref "USBA1") (pin "4") (pinfunction "GND_4") (pintype "passive"))
      (node (ref "k1") (pin "2") (pinfunction "2_2") (pintype "passive"))
      (node (ref "k2") (pin "2") (pinfunction "2_2") (pintype "passive"))
      (node (ref "k3") (pin "2") (pinfunction "2_2") (pintype "passive"))
      (node (ref "k4") (pin "1") (pinfunction "1_1") (pintype "passive"))
      (node (ref "k5") (pin "2") (pinfunction "2_2") (pintype "passive"))
      (node (ref "port1") (pin "5") (pinfunction "GND_5") (pintype "power_in"))
      (node (ref "port1") (pin "6") (pinfunction "SHLD_6") (pintype "passive"))
      (node (ref "port1") (pin "7") (pinfunction "SHLD_7") (pintype "passive"))
      (node (ref "port2") (pin "5") (pinfunction "GND_5") (pintype "power_in"))
      (node (ref "port2") (pin "6") (pinfunction "SHLD_6") (pintype "passive"))
      (node (ref "port2") (pin "7") (pinfunction "SHLD_7") (pintype "passive"))
      (node (ref "port3") (pin "5") (pinfunction "GND_5") (pintype "power_in"))
      (node (ref "port3") (pin "6") (pinfunction "SHLD_6") (pintype "passive"))
      (node (ref "port3") (pin "7") (pinfunction "SHLD_7") (pintype "passive"))
      (node (ref "port4") (pin "5") (pinfunction "GND_5") (pintype "power_in"))
      (node (ref "port4") (pin "6") (pinfunction "SHLD_6") (pintype "passive"))
      (node (ref "port4") (pin "7") (pinfunction "SHLD_7") (pintype "passive"))
    )
    (net (code "75") (name "Net-(D4-A)") (class "Default")
      (node (ref "D4") (pin "1") (pinfunction "A_1") (pintype "passive"))
      (node (ref "R4") (pin "2") (pinfunction "2_2") (pintype "passive"))
    )
    (net (code "76") (name "Net-(D41-A)") (class "Default")
      (node (ref "D41") (pin "1") (pinfunction "A_1") (pintype "passive"))
      (node (ref "R41") (pin "2") (pinfunction "2_2") (pintype "passive"))
    )
    (net (code "77") (name "Net-(Q61-B)") (class "Default")
      (node (ref "Q61") (pin "1") (pinfunction "B_1") (pintype "passive"))
      (node (ref "R77") (pin "1") (pintype "passive"))
    )
    (net (code "78") (name "Net-(Q71-B)") (class "Default")
      (node (ref "Q71") (pin "1") (pinfunction "B_1") (pintype "passive"))
      (node (ref "R72") (pin "1") (pintype "passive"))
      (node (ref "R74") (pin "2") (pintype "passive"))
    )
    (net (code "79") (name "Net-(Q71-C)") (class "Default")
      (node (ref "Q71") (pin "3") (pinfunction "C_3") (pintype "passive"))
      (node (ref "Q74") (pin "1") (pinfunction "B_1") (pintype "passive"))
      (node (ref "R71") (pin "2") (pinfunction "2_2") (pintype "passive"))
      (node (ref "R73") (pin "2") (pintype "passive"))
    )
    (net (code "80") (name "Net-(U27-VCP)") (class "Default")
      (node (ref "C32") (pin "1") (pinfunction "1_1") (pintype "passive"))
      (node (ref "U27") (pin "11") (pinfunction "VCP_11") (pintype "passive"))
    )
    (net (code "81") (name "Net-(U27-VINT)") (class "Default")
      (node (ref "C33") (pin "2") (pinfunction "2_2") (pintype "passive"))
      (node (ref "U27") (pin "14") (pinfunction "VINT_14") (pintype "passive"))
    )
    (net (code "82") (name "Net-(U28-VCP)") (class "Default")
      (node (ref "C35") (pin "1") (pinfunction "1_1") (pintype "passive"))
      (node (ref "U28") (pin "11") (pinfunction "VCP_11") (pintype "passive"))
    )
    (net (code "83") (name "Net-(U28-VINT)") (class "Default")
      (node (ref "C36") (pin "2") (pinfunction "2_2") (pintype "passive"))
      (node (ref "U28") (pin "14") (pinfunction "VINT_14") (pintype "passive"))
    )
    (net (code "84") (name "unconnected-(LCD1-ROM_CS-Pad4)") (class "Default")
      (node (ref "LCD1") (pin "4") (pinfunction "ROM_CS_4") (pintype "passive"))
    )
    (net (code "85") (name "unconnected-(LCD1-ROM_IN-Pad1)") (class "Default")
      (node (ref "LCD1") (pin "1") (pinfunction "ROM_IN_1") (pintype "passive"))
    )
    (net (code "86") (name "unconnected-(LCD1-ROM_OUT-Pad2)") (class "Default")
      (node (ref "LCD1") (pin "2") (pinfunction "ROM_OUT_2") (pintype "passive"))
    )
    (net (code "87") (name "unconnected-(LCD1-ROM_SCK-Pad3)") (class "Default")
      (node (ref "LCD1") (pin "3") (pinfunction "ROM_SCK_3") (pintype "passive"))
    )
    (net (code "88") (name "unconnected-(PortA-SHLD-Pad7)") (class "Default")
      (node (ref "PortA") (pin "7") (pinfunction "SHLD_7") (pintype "passive"))
    )
    (net (code "89") (name "unconnected-(PortB-SHLD-Pad7)") (class "Default")
      (node (ref "PortB") (pin "7") (pinfunction "SHLD_7") (pintype "passive"))
    )
    (net (code "90") (name "unconnected-(PortC-SHLD-Pad7)") (class "Default")
      (node (ref "PortC") (pin "7") (pinfunction "SHLD_7") (pintype "passive"))
    )
    (net (code "91") (name "unconnected-(PortD-SHLD-Pad7)") (class "Default")
      (node (ref "PortD") (pin "7") (pinfunction "SHLD_7") (pintype "passive"))
    )
    (net (code "92") (name "unconnected-(U1-PA2-Pad12)") (class "Default")
      (node (ref "U1") (pin "12") (pinfunction "PA2_12") (pintype "bidirectional"))
    )
    (net (code "93") (name "unconnected-(U1-PA3-Pad13)") (class "Default")
      (node (ref "U1") (pin "13") (pinfunction "PA3_13") (pintype "bidirectional"))
    )
    (net (code "94") (name "unconnected-(U1-PA8-Pad29)") (class "Default")
      (node (ref "U1") (pin "29") (pinfunction "PA8_29") (pintype "bidirectional"))
    )
    (net (code "95") (name "unconnected-(U1-PA11-Pad32)") (class "Default")
      (node (ref "U1") (pin "32") (pinfunction "PA11_32") (pintype "bidirectional"))
    )
    (net (code "96") (name "unconnected-(U1-PB2{slash}BOOT1-Pad20)") (class "Default")
      (node (ref "U1") (pin "20") (pinfunction "PB2/BOOT1_20") (pintype "bidirectional"))
    )
    (net (code "97") (name "unconnected-(U1-PB8-Pad45)") (class "Default")
      (node (ref "U1") (pin "45") (pinfunction "PB8_45") (pintype "bidirectional"))
    )
    (net (code "98") (name "unconnected-(U1-PB9-Pad46)") (class "Default")
      (node (ref "U1") (pin "46") (pinfunction "PB9_46") (pintype "bidirectional"))
    )
    (net (code "99") (name "unconnected-(U1-PB10-Pad21)") (class "Default")
      (node (ref "U1") (pin "21") (pinfunction "PB10_21") (pintype "bidirectional"))
    )
    (net (code "100") (name "unconnected-(U1-PB11-Pad22)") (class "Default")
      (node (ref "U1") (pin "22") (pinfunction "PB11_22") (pintype "bidirectional"))
    )
    (net (code "101") (name "unconnected-(U1-PB12-Pad25)") (class "Default")
      (node (ref "U1") (pin "25") (pinfunction "PB12_25") (pintype "bidirectional"))
    )
    (net (code "102") (name "unconnected-(U1-PB13-Pad26)") (class "Default")
      (node (ref "U1") (pin "26") (pinfunction "PB13_26") (pintype "bidirectional"))
    )
    (net (code "103") (name "unconnected-(U1-PB14-Pad27)") (class "Default")
      (node (ref "U1") (pin "27") (pinfunction "PB14_27") (pintype "bidirectional"))
    )
    (net (code "104") (name "unconnected-(U1-PB15-Pad28)") (class "Default")
      (node (ref "U1") (pin "28") (pinfunction "PB15_28") (pintype "bidirectional"))
    )
    (net (code "105") (name "unconnected-(U3-PB1-Pad14)") (class "Default")
      (node (ref "U3") (pin "14") (pinfunction "PB1_14") (pintype "bidirectional"))
    )
    (net (code "106") (name "unconnected-(U27-nFAULT-Pad8)") (class "Default")
      (node (ref "U27") (pin "8") (pinfunction "nFAULT_8") (pintype "passive"))
    )
    (net (code "107") (name "unconnected-(U28-nFAULT-Pad8)") (class "Default")
      (node (ref "U28") (pin "8") (pinfunction "nFAULT_8") (pintype "passive"))
    )
    (net (code "108") (name "unconnected-(port2-SHLD-Pad4)") (class "Default")
      (node (ref "port2") (pin "4") (pinfunction "SHLD_4") (pintype "passive"))
    )
    (net (code "109") (name "unconnected-(port3-SHLD-Pad4)") (class "Default")
      (node (ref "port3") (pin "4") (pinfunction "SHLD_4") (pintype "passive"))
    )
    (net (code "110") (name "unconnected-(port4-SHLD-Pad4)") (class "Default")
      (node (ref "port4") (pin "4") (pinfunction "SHLD_4") (pintype "passive"))
    )
  )
)
